# 23_SFP_PORTS.net
KiCad netlist of a schematic drawn in Altium Designer
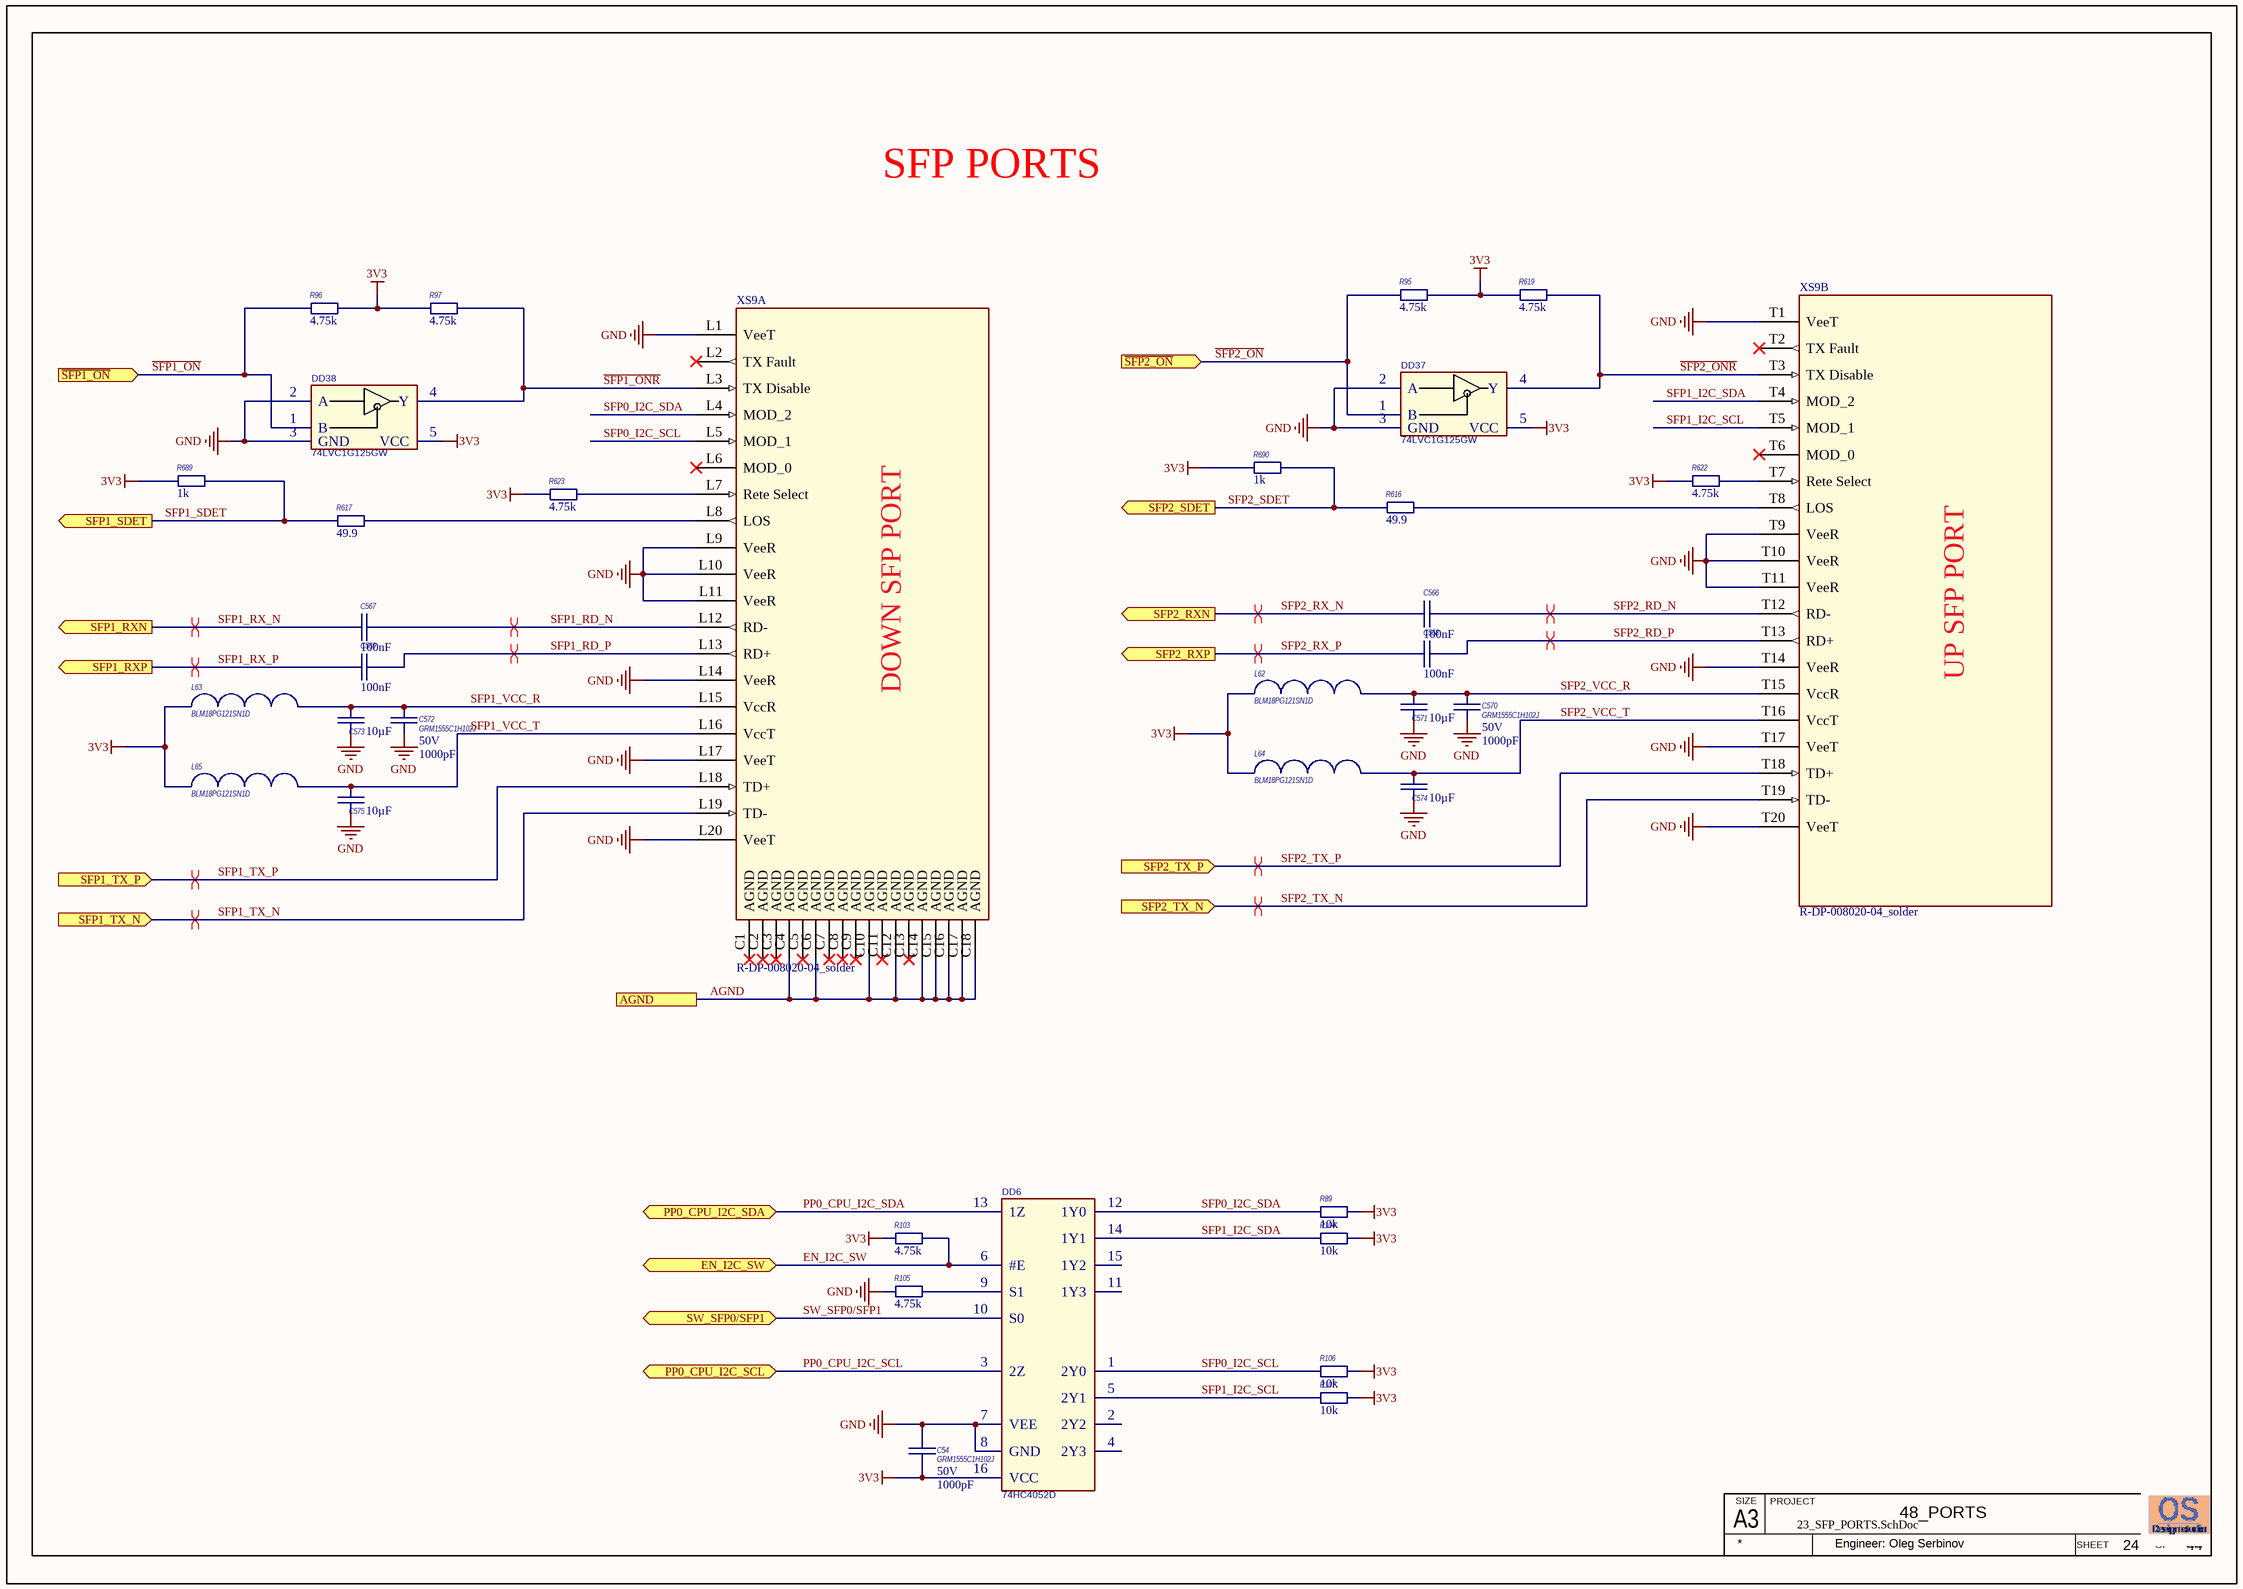
[diagram p0: 23_SFP_PORTS.SchDoc]

(export (version "E")
  (design (tool "Eeschema 10.0.6"))
  (components
    (comp (ref "C54")
      (value "GRM1555C1H102J")
      (footprint "CAPC1005[0402]")
      (description "C0402, 1nF 5%, 50V, C0G")
      (fields
        (field (name "TOLERANCE") "±5%")
        (field (name "MANUFACTURER") "Murata")
        (field (name "VOLTAGE - RATED") "50V")
        (field (name "CAPACITANCE") "1000pF")
      )
      (libsource (lib "CAPACITORS") (part "GRM1555C1H102J"))
    )
    (comp (ref "C566")
      (value "GRM155R71E104KE14D")
      (footprint "C0402_IPC High Density")
      (description "C0402, 100nF, 25V, X7R")
      (fields
        (field (name "MANUFACTURER") "Murata")
        (field (name "CAPACITANCE") "100nF")
        (field (name "CUSTOMER PART NUMBER") "Конденсатор, 100n, 0402, 25V, X7R, 10%")
      )
      (libsource (lib "CAPACITORS") (part "GRM155R71E104KE14D"))
    )
    (comp (ref "C567")
      (value "GRM155R71E104KE14D")
      (footprint "C0402_IPC High Density")
      (description "C0402, 100nF, 25V, X7R")
      (fields
        (field (name "MANUFACTURER") "Murata")
        (field (name "CAPACITANCE") "100nF")
        (field (name "CUSTOMER PART NUMBER") "Конденсатор, 100n, 0402, 25V, X7R, 10%")
      )
      (libsource (lib "CAPACITORS") (part "GRM155R71E104KE14D"))
    )
    (comp (ref "C568")
      (value "GRM155R71E104KE14D")
      (footprint "C0402_IPC High Density")
      (description "C0402, 100nF, 25V, X7R")
      (fields
        (field (name "MANUFACTURER") "Murata")
        (field (name "CAPACITANCE") "100nF")
        (field (name "CUSTOMER PART NUMBER") "Конденсатор, 100n, 0402, 25V, X7R, 10%")
      )
      (libsource (lib "CAPACITORS") (part "GRM155R71E104KE14D"))
    )
    (comp (ref "C569")
      (value "GRM155R71E104KE14D")
      (footprint "C0402_IPC High Density")
      (description "C0402, 100nF, 25V, X7R")
      (fields
        (field (name "MANUFACTURER") "Murata")
        (field (name "CAPACITANCE") "100nF")
        (field (name "CUSTOMER PART NUMBER") "Конденсатор, 100n, 0402, 25V, X7R, 10%")
      )
      (libsource (lib "CAPACITORS") (part "GRM155R71E104KE14D"))
    )
    (comp (ref "C570")
      (value "GRM1555C1H102J")
      (footprint "CAPC1005[0402]")
      (description "C0402, 1nF 5%, 50V, C0G")
      (fields
        (field (name "TOLERANCE") "±5%")
        (field (name "MANUFACTURER") "Murata")
        (field (name "VOLTAGE - RATED") "50V")
        (field (name "CAPACITANCE") "1000pF")
      )
      (libsource (lib "CAPACITORS") (part "GRM1555C1H102J"))
    )
    (comp (ref "C571")
      (value "GRM21BR61C106KE15")
      (footprint "CAPC2012[0805]")
      (description "C0805, 10uF 10%, 16V, X5R")
      (fields
        (field (name "MANUFACTURER") "Murata")
        (field (name "TOLERANCE") "±10%")
        (field (name "CAPACITANCE") "10µF")
      )
      (libsource (lib "CAPACITORS") (part "GRM21BR61C106KE15"))
    )
    (comp (ref "C572")
      (value "GRM1555C1H102J")
      (footprint "CAPC1005[0402]")
      (description "C0402, 1nF 5%, 50V, C0G")
      (fields
        (field (name "TOLERANCE") "±5%")
        (field (name "MANUFACTURER") "Murata")
        (field (name "VOLTAGE - RATED") "50V")
        (field (name "CAPACITANCE") "1000pF")
      )
      (libsource (lib "CAPACITORS") (part "GRM1555C1H102J"))
    )
    (comp (ref "C573")
      (value "GRM21BR61C106KE15")
      (footprint "CAPC2012[0805]")
      (description "C0805, 10uF 10%, 16V, X5R")
      (fields
        (field (name "MANUFACTURER") "Murata")
        (field (name "TOLERANCE") "±10%")
        (field (name "CAPACITANCE") "10µF")
      )
      (libsource (lib "CAPACITORS") (part "GRM21BR61C106KE15"))
    )
    (comp (ref "C574")
      (value "GRM21BR61C106KE15")
      (footprint "CAPC2012[0805]")
      (description "C0805, 10uF 10%, 16V, X5R")
      (fields
        (field (name "MANUFACTURER") "Murata")
        (field (name "TOLERANCE") "±10%")
        (field (name "CAPACITANCE") "10µF")
      )
      (libsource (lib "CAPACITORS") (part "GRM21BR61C106KE15"))
    )
    (comp (ref "C575")
      (value "GRM21BR61C106KE15")
      (footprint "CAPC2012[0805]")
      (description "C0805, 10uF 10%, 16V, X5R")
      (fields
        (field (name "MANUFACTURER") "Murata")
        (field (name "TOLERANCE") "±10%")
        (field (name "CAPACITANCE") "10µF")
      )
      (libsource (lib "CAPACITORS") (part "GRM21BR61C106KE15"))
    )
    (comp (ref "DD6")
      (value "74HC4052D")
      (footprint "SOIC-16")
      (description "IC MUX/DEMUX DUAL 4X1, 16SOIC")
      (fields
        (field (name "CUSTOMER PART NUMBER") "Микросхема, 74HC4052D, IC MUX/DEMUX DUAL 4X1, 16-SOIC")
        (field (name "MANUFACTURER") "NXP Semiconductors")
      )
      (libsource (lib "DIGITAL and ANALIG ICs") (part "74HC4052D"))
    )
    (comp (ref "DD37")
      (value "74LVC1G125GW")
      (footprint "TSSOP5 (SOT353)")
      (description "IC Bus buffer/line driver 3-state, TSSOP5")
      (fields
        (field (name "MANUFACTURER") "NXP Semiconductors")
        (field (name "CUSTOMER PART NUMBER") "Микросхема, 74LVC1G125GW, IC BUFF DVR TRI-ST N-INV, 5-TSSOP")
      )
      (libsource (lib "DIGITAL and ANALIG ICs") (part "74LVC1G125GW"))
    )
    (comp (ref "DD38")
      (value "74LVC1G125GW")
      (footprint "TSSOP5 (SOT353)")
      (description "IC Bus buffer/line driver 3-state, TSSOP5")
      (fields
        (field (name "MANUFACTURER") "NXP Semiconductors")
        (field (name "CUSTOMER PART NUMBER") "Микросхема, 74LVC1G125GW, IC BUFF DVR TRI-ST N-INV, 5-TSSOP")
      )
      (libsource (lib "DIGITAL and ANALIG ICs") (part "74LVC1G125GW"))
    )
    (comp (ref "L62")
      (value "BLM18PG121SN1D")
      (footprint "INDC1608X95N")
      (description "FILTER BLM18 (0603, 2A)")
      (fields
        (field (name "MANUFACTURER") "Murata")
        (field (name "RPART NUMBER") "MPZ1608S121ATAH0 ; CIC10P121NC ; MPZ1608S121ATDH5 ; BLM18PG121SH1D ; 742792625")
      )
      (libsource (lib "INDUCTORS") (part "BLM18PG121SN1D"))
    )
    (comp (ref "L63")
      (value "BLM18PG121SN1D")
      (footprint "INDC1608X95N")
      (description "FILTER BLM18 (0603, 2A)")
      (fields
        (field (name "MANUFACTURER") "Murata")
        (field (name "RPART NUMBER") "MPZ1608S121ATAH0 ; CIC10P121NC ; MPZ1608S121ATDH5 ; BLM18PG121SH1D ; 742792625")
      )
      (libsource (lib "INDUCTORS") (part "BLM18PG121SN1D"))
    )
    (comp (ref "L64")
      (value "BLM18PG121SN1D")
      (footprint "INDC1608X95N")
      (description "FILTER BLM18 (0603, 2A)")
      (fields
        (field (name "MANUFACTURER") "Murata")
        (field (name "RPART NUMBER") "MPZ1608S121ATAH0 ; CIC10P121NC ; MPZ1608S121ATDH5 ; BLM18PG121SH1D ; 742792625")
      )
      (libsource (lib "INDUCTORS") (part "BLM18PG121SN1D"))
    )
    (comp (ref "L65")
      (value "BLM18PG121SN1D")
      (footprint "INDC1608X95N")
      (description "FILTER BLM18 (0603, 2A)")
      (fields
        (field (name "MANUFACTURER") "Murata")
        (field (name "RPART NUMBER") "MPZ1608S121ATAH0 ; CIC10P121NC ; MPZ1608S121ATDH5 ; BLM18PG121SH1D ; 742792625")
      )
      (libsource (lib "INDUCTORS") (part "BLM18PG121SN1D"))
    )
    (comp (ref "R89")
      (value "ERJ-2RKF1002X")
      (footprint "R0402_IPC High Density")
      (description "R0402, 10k 1%")
      (fields
        (field (name "MANUFACTURER") "Panasonic")
        (field (name "TOLERANCE") "1 %")
        (field (name "RESISTANCE") "10k")
      )
      (libsource (lib "RESISTOR") (part "ERJ-2RKF1002X"))
    )
    (comp (ref "R95")
      (value "ERJ-2RKF4751X")
      (footprint "R0402_IPC High Density")
      (description "R0402, 4.75k 1%")
      (fields
        (field (name "TOLERANCE") "±1%")
        (field (name "MANUFACTURER") "Panasonic")
        (field (name "RESISTANCE (OHMS)") "4.75k")
      )
      (libsource (lib "RESISTOR") (part "ERJ-2RKF4751X"))
    )
    (comp (ref "R96")
      (value "ERJ-2RKF4751X")
      (footprint "R0402_IPC High Density")
      (description "R0402, 4.75k 1%")
      (fields
        (field (name "TOLERANCE") "±1%")
        (field (name "MANUFACTURER") "Panasonic")
        (field (name "RESISTANCE (OHMS)") "4.75k")
      )
      (libsource (lib "RESISTOR") (part "ERJ-2RKF4751X"))
    )
    (comp (ref "R97")
      (value "ERJ-2RKF4751X")
      (footprint "R0402_IPC High Density")
      (description "R0402, 4.75k 1%")
      (fields
        (field (name "TOLERANCE") "±1%")
        (field (name "MANUFACTURER") "Panasonic")
        (field (name "RESISTANCE (OHMS)") "4.75k")
      )
      (libsource (lib "RESISTOR") (part "ERJ-2RKF4751X"))
    )
    (comp (ref "R103")
      (value "ERJ-2RKF4751X")
      (footprint "R0402_IPC High Density")
      (description "R0402, 4.75k 1%")
      (fields
        (field (name "TOLERANCE") "±1%")
        (field (name "MANUFACTURER") "Panasonic")
        (field (name "RESISTANCE (OHMS)") "4.75k")
      )
      (libsource (lib "RESISTOR") (part "ERJ-2RKF4751X"))
    )
    (comp (ref "R104")
      (value "ERJ-2RKF1002X")
      (footprint "R0402_IPC High Density")
      (description "R0402, 10k 1%")
      (fields
        (field (name "MANUFACTURER") "Panasonic")
        (field (name "TOLERANCE") "1 %")
        (field (name "RESISTANCE") "10k")
      )
      (libsource (lib "RESISTOR") (part "ERJ-2RKF1002X"))
    )
    (comp (ref "R105")
      (value "ERJ-2RKF4751X")
      (footprint "R0402_IPC High Density")
      (description "R0402, 4.75k 1%")
      (fields
        (field (name "TOLERANCE") "±1%")
        (field (name "MANUFACTURER") "Panasonic")
        (field (name "RESISTANCE (OHMS)") "4.75k")
      )
      (libsource (lib "RESISTOR") (part "ERJ-2RKF4751X"))
    )
    (comp (ref "R106")
      (value "ERJ-2RKF1002X")
      (footprint "R0402_IPC High Density")
      (description "R0402, 10k 1%")
      (fields
        (field (name "MANUFACTURER") "Panasonic")
        (field (name "TOLERANCE") "1 %")
        (field (name "RESISTANCE") "10k")
      )
      (libsource (lib "RESISTOR") (part "ERJ-2RKF1002X"))
    )
    (comp (ref "R107")
      (value "ERJ-2RKF1002X")
      (footprint "R0402_IPC High Density")
      (description "R0402, 10k 1%")
      (fields
        (field (name "MANUFACTURER") "Panasonic")
        (field (name "TOLERANCE") "1 %")
        (field (name "RESISTANCE") "10k")
      )
      (libsource (lib "RESISTOR") (part "ERJ-2RKF1002X"))
    )
    (comp (ref "R616")
      (value "ERJ-2RKF49R9X")
      (footprint "R0402_IPC High Density")
      (description "R0402, 49.9R 1%")
      (fields
        (field (name "MANUFACTURER") "Panasonic")
        (field (name "TOLERANCE") "1 %")
        (field (name "RESISTANCE") "49.9")
      )
      (libsource (lib "RESISTOR") (part "ERJ-2RKF49R9X"))
    )
    (comp (ref "R617")
      (value "ERJ-2RKF49R9X")
      (footprint "R0402_IPC High Density")
      (description "R0402, 49.9R 1%")
      (fields
        (field (name "MANUFACTURER") "Panasonic")
        (field (name "TOLERANCE") "1 %")
        (field (name "RESISTANCE") "49.9")
      )
      (libsource (lib "RESISTOR") (part "ERJ-2RKF49R9X"))
    )
    (comp (ref "R619")
      (value "ERJ-2RKF4751X")
      (footprint "R0402_IPC High Density")
      (description "R0402, 4.75k 1%")
      (fields
        (field (name "TOLERANCE") "±1%")
        (field (name "MANUFACTURER") "Panasonic")
        (field (name "RESISTANCE (OHMS)") "4.75k")
      )
      (libsource (lib "RESISTOR") (part "ERJ-2RKF4751X"))
    )
    (comp (ref "R622")
      (value "ERJ-2RKF4751X")
      (footprint "R0402_IPC High Density")
      (description "R0402, 4.75k 1%")
      (fields
        (field (name "TOLERANCE") "±1%")
        (field (name "MANUFACTURER") "Panasonic")
        (field (name "RESISTANCE (OHMS)") "4.75k")
      )
      (libsource (lib "RESISTOR") (part "ERJ-2RKF4751X"))
    )
    (comp (ref "R623")
      (value "ERJ-2RKF4751X")
      (footprint "R0402_IPC High Density")
      (description "R0402, 4.75k 1%")
      (fields
        (field (name "TOLERANCE") "±1%")
        (field (name "MANUFACTURER") "Panasonic")
        (field (name "RESISTANCE (OHMS)") "4.75k")
      )
      (libsource (lib "RESISTOR") (part "ERJ-2RKF4751X"))
    )
    (comp (ref "R689")
      (value "ERJ-2RKF1001X")
      (footprint "R0402_IPC High Density")
      (description "R0402, 1k 1%")
      (fields
        (field (name "MANUFACTURER") "Panasonic")
        (field (name "TOLERANCE") "1 %")
        (field (name "RESISTANCE") "1k")
      )
      (libsource (lib "RESISTOR") (part "ERJ-2RKF1001X"))
    )
    (comp (ref "R690")
      (value "ERJ-2RKF1001X")
      (footprint "R0402_IPC High Density")
      (description "R0402, 1k 1%")
      (fields
        (field (name "MANUFACTURER") "Panasonic")
        (field (name "TOLERANCE") "1 %")
        (field (name "RESISTANCE") "1k")
      )
      (libsource (lib "RESISTOR") (part "ERJ-2RKF1001X"))
    )
    (comp (ref "XS9")
      (value "R-DP-008020-04_solder")
      (footprint "R-DP-008020-04_solder")
      (description "Connector SFP CAGE 2X1 PRESS FIT")
      (fields
        (field (name "CUSTOMER PART NUMBER") "Разъем, R-DP-008020-04, SFP 2X1 Stacked Cage, PRESS FIT")
        (field (name "MANUFACTURER") "ALL BEST")
      )
      (libsource (lib "CONNECTORS") (part "R-DP-008020-04_solder"))
    )
  )
  (nets
    (net (code "1") (name "/AGND") (class "Default")
      (node (ref "XS9") (pin "C10") (pinfunction "AGND_C10") (pintype "power_in"))
      (node (ref "XS9") (pin "C12") (pinfunction "AGND_C12") (pintype "power_in"))
      (node (ref "XS9") (pin "C14") (pinfunction "AGND_C14") (pintype "power_in"))
      (node (ref "XS9") (pin "C15") (pinfunction "AGND_C15") (pintype "power_in"))
      (node (ref "XS9") (pin "C16") (pinfunction "AGND_C16") (pintype "power_in"))
      (node (ref "XS9") (pin "C17") (pinfunction "AGND_C17") (pintype "power_in"))
      (node (ref "XS9") (pin "C18") (pinfunction "AGND_C18") (pintype "power_in"))
      (node (ref "XS9") (pin "C4") (pinfunction "AGND_C4") (pintype "power_in"))
      (node (ref "XS9") (pin "C6") (pinfunction "AGND_C6") (pintype "power_in"))
    )
    (net (code "2") (name "/EN_I2C_SW") (class "Default")
      (node (ref "DD6") (pin "6") (pinfunction "#E_6") (pintype "passive"))
      (node (ref "R103") (pin "2") (pintype "passive"))
    )
    (net (code "3") (name "/PP0_CPU_I2C_SCL") (class "Default")
      (node (ref "DD6") (pin "3") (pinfunction "2Z_3") (pintype "passive"))
    )
    (net (code "4") (name "/PP0_CPU_I2C_SDA") (class "Default")
      (node (ref "DD6") (pin "13") (pinfunction "1Z_13") (pintype "passive"))
    )
    (net (code "5") (name "/SFP0_I2C_SCL") (class "Default")
      (node (ref "DD6") (pin "1") (pinfunction "2Y0_1") (pintype "passive"))
      (node (ref "R106") (pin "2") (pintype "passive"))
      (node (ref "XS9") (pin "L5") (pinfunction "MOD_1_L5") (pintype "input"))
    )
    (net (code "6") (name "/SFP0_I2C_SDA") (class "Default")
      (node (ref "DD6") (pin "12") (pinfunction "1Y0_12") (pintype "passive"))
      (node (ref "R89") (pin "2") (pintype "passive"))
      (node (ref "XS9") (pin "L4") (pinfunction "MOD_2_L4") (pintype "input"))
    )
    (net (code "7") (name "/SFP1_I2C_SCL") (class "Default")
      (node (ref "DD6") (pin "5") (pinfunction "2Y1_5") (pintype "passive"))
      (node (ref "R107") (pin "2") (pintype "passive"))
      (node (ref "XS9") (pin "T5") (pinfunction "MOD_1_T5") (pintype "input"))
    )
    (net (code "8") (name "/SFP1_I2C_SDA") (class "Default")
      (node (ref "DD6") (pin "14") (pinfunction "1Y1_14") (pintype "passive"))
      (node (ref "R104") (pin "2") (pintype "passive"))
      (node (ref "XS9") (pin "T4") (pinfunction "MOD_2_T4") (pintype "input"))
    )
    (net (code "9") (name "/SFP1_ON") (class "Default")
      (node (ref "DD38") (pin "1") (pinfunction "B_1") (pintype "passive"))
      (node (ref "R96") (pin "1") (pintype "passive"))
    )
    (net (code "10") (name "/SFP1_ONR") (class "Default")
      (node (ref "DD38") (pin "4") (pinfunction "Y_4") (pintype "passive"))
      (node (ref "R97") (pin "2") (pintype "passive"))
      (node (ref "XS9") (pin "L3") (pinfunction "TX_Disable_L3") (pintype "input"))
    )
    (net (code "11") (name "/SFP1_RD_N") (class "Default")
      (node (ref "C567") (pin "1") (pintype "passive"))
      (node (ref "XS9") (pin "L12") (pinfunction "RD-_L12") (pintype "output"))
    )
    (net (code "12") (name "/SFP1_RD_P") (class "Default")
      (node (ref "C569") (pin "1") (pintype "passive"))
      (node (ref "XS9") (pin "L13") (pinfunction "RD+_L13") (pintype "output"))
    )
    (net (code "13") (name "/SFP1_RX_N") (class "Default") (node (ref "C567") (pin "2") (pintype "passive")))
    (net (code "14") (name "/SFP1_RX_P") (class "Default") (node (ref "C569") (pin "2") (pintype "passive")))
    (net (code "15") (name "/SFP1_SDET") (class "Default")
      (node (ref "R617") (pin "1") (pintype "passive"))
      (node (ref "R689") (pin "2") (pintype "passive"))
    )
    (net (code "16") (name "/SFP1_TX_N") (class "Default")
      (node (ref "XS9") (pin "L19") (pinfunction "TD-_L19") (pintype "input"))
    )
    (net (code "17") (name "/SFP1_TX_P") (class "Default")
      (node (ref "XS9") (pin "L18") (pinfunction "TD+_L18") (pintype "input"))
    )
    (net (code "18") (name "/SFP1_VCC_R") (class "Default")
      (node (ref "C572") (pin "2") (pintype "passive"))
      (node (ref "C573") (pin "2") (pintype "passive"))
      (node (ref "L63") (pin "2") (pinfunction "2_2") (pintype "passive"))
      (node (ref "XS9") (pin "L15") (pinfunction "VccR_L15") (pintype "power_in"))
    )
    (net (code "19") (name "/SFP1_VCC_T") (class "Default")
      (node (ref "C575") (pin "1") (pintype "passive"))
      (node (ref "L65") (pin "2") (pinfunction "2_2") (pintype "passive"))
      (node (ref "XS9") (pin "L16") (pinfunction "VccT_L16") (pintype "power_in"))
    )
    (net (code "20") (name "/SFP2_ON") (class "Default")
      (node (ref "DD37") (pin "1") (pinfunction "B_1") (pintype "passive"))
      (node (ref "R95") (pin "1") (pintype "passive"))
    )
    (net (code "21") (name "/SFP2_ONR") (class "Default")
      (node (ref "DD37") (pin "4") (pinfunction "Y_4") (pintype "passive"))
      (node (ref "R619") (pin "2") (pintype "passive"))
      (node (ref "XS9") (pin "T3") (pinfunction "TX_Disable_T3") (pintype "input"))
    )
    (net (code "22") (name "/SFP2_RD_N") (class "Default")
      (node (ref "C566") (pin "1") (pintype "passive"))
      (node (ref "XS9") (pin "T12") (pinfunction "RD-_T12") (pintype "output"))
    )
    (net (code "23") (name "/SFP2_RD_P") (class "Default")
      (node (ref "C568") (pin "1") (pintype "passive"))
      (node (ref "XS9") (pin "T13") (pinfunction "RD+_T13") (pintype "output"))
    )
    (net (code "24") (name "/SFP2_RX_N") (class "Default") (node (ref "C566") (pin "2") (pintype "passive")))
    (net (code "25") (name "/SFP2_RX_P") (class "Default") (node (ref "C568") (pin "2") (pintype "passive")))
    (net (code "26") (name "/SFP2_SDET") (class "Default")
      (node (ref "R616") (pin "1") (pintype "passive"))
      (node (ref "R690") (pin "2") (pintype "passive"))
    )
    (net (code "27") (name "/SFP2_TX_N") (class "Default")
      (node (ref "XS9") (pin "T19") (pinfunction "TD-_T19") (pintype "input"))
    )
    (net (code "28") (name "/SFP2_TX_P") (class "Default")
      (node (ref "XS9") (pin "T18") (pinfunction "TD+_T18") (pintype "input"))
    )
    (net (code "29") (name "/SFP2_VCC_R") (class "Default")
      (node (ref "C570") (pin "2") (pintype "passive"))
      (node (ref "C571") (pin "2") (pintype "passive"))
      (node (ref "L62") (pin "2") (pinfunction "2_2") (pintype "passive"))
      (node (ref "XS9") (pin "T15") (pinfunction "VccR_T15") (pintype "power_in"))
    )
    (net (code "30") (name "/SFP2_VCC_T") (class "Default")
      (node (ref "C574") (pin "1") (pintype "passive"))
      (node (ref "L64") (pin "2") (pinfunction "2_2") (pintype "passive"))
      (node (ref "XS9") (pin "T16") (pinfunction "VccT_T16") (pintype "power_in"))
    )
    (net (code "31") (name "/SW_SFP0{slash}SFP1") (class "Default")
      (node (ref "DD6") (pin "10") (pinfunction "S0_10") (pintype "passive"))
    )
    (net (code "32") (name "3V3") (class "Default")
      (node (ref "C54") (pin "2") (pintype "passive"))
      (node (ref "DD37") (pin "5") (pinfunction "VCC_5") (pintype "passive"))
      (node (ref "DD38") (pin "5") (pinfunction "VCC_5") (pintype "passive"))
      (node (ref "DD6") (pin "16") (pinfunction "VCC_16") (pintype "passive"))
      (node (ref "L62") (pin "1") (pinfunction "1_1") (pintype "passive"))
      (node (ref "L63") (pin "1") (pinfunction "1_1") (pintype "passive"))
      (node (ref "L64") (pin "1") (pinfunction "1_1") (pintype "passive"))
      (node (ref "L65") (pin "1") (pinfunction "1_1") (pintype "passive"))
      (node (ref "R103") (pin "1") (pintype "passive"))
      (node (ref "R104") (pin "1") (pintype "passive"))
      (node (ref "R106") (pin "1") (pintype "passive"))
      (node (ref "R107") (pin "1") (pintype "passive"))
      (node (ref "R619") (pin "1") (pintype "passive"))
      (node (ref "R622") (pin "1") (pintype "passive"))
      (node (ref "R623") (pin "1") (pintype "passive"))
      (node (ref "R689") (pin "1") (pintype "passive"))
      (node (ref "R690") (pin "1") (pintype "passive"))
      (node (ref "R89") (pin "1") (pintype "passive"))
      (node (ref "R95") (pin "2") (pintype "passive"))
      (node (ref "R96") (pin "2") (pintype "passive"))
      (node (ref "R97") (pin "1") (pintype "passive"))
    )
    (net (code "33") (name "GND") (class "Default")
      (node (ref "C54") (pin "1") (pintype "passive"))
      (node (ref "C570") (pin "1") (pintype "passive"))
      (node (ref "C571") (pin "1") (pintype "passive"))
      (node (ref "C572") (pin "1") (pintype "passive"))
      (node (ref "C573") (pin "1") (pintype "passive"))
      (node (ref "C574") (pin "2") (pintype "passive"))
      (node (ref "C575") (pin "2") (pintype "passive"))
      (node (ref "DD37") (pin "2") (pinfunction "A_2") (pintype "passive"))
      (node (ref "DD37") (pin "3") (pinfunction "GND_3") (pintype "passive"))
      (node (ref "DD38") (pin "2") (pinfunction "A_2") (pintype "passive"))
      (node (ref "DD38") (pin "3") (pinfunction "GND_3") (pintype "passive"))
      (node (ref "DD6") (pin "7") (pinfunction "VEE_7") (pintype "passive"))
      (node (ref "DD6") (pin "8") (pinfunction "GND_8") (pintype "passive"))
      (node (ref "R105") (pin "1") (pintype "passive"))
      (node (ref "XS9") (pin "L1") (pinfunction "VeeT_L1") (pintype "power_in"))
      (node (ref "XS9") (pin "L10") (pinfunction "VeeR_L10") (pintype "power_in"))
      (node (ref "XS9") (pin "L11") (pinfunction "VeeR_L11") (pintype "power_in"))
      (node (ref "XS9") (pin "L14") (pinfunction "VeeR_L14") (pintype "power_in"))
      (node (ref "XS9") (pin "L17") (pinfunction "VeeT_L17") (pintype "power_in"))
      (node (ref "XS9") (pin "L20") (pinfunction "VeeT_L20") (pintype "power_in"))
      (node (ref "XS9") (pin "L9") (pinfunction "VeeR_L9") (pintype "power_in"))
      (node (ref "XS9") (pin "T1") (pinfunction "VeeT_T1") (pintype "power_in"))
      (node (ref "XS9") (pin "T10") (pinfunction "VeeR_T10") (pintype "power_in"))
      (node (ref "XS9") (pin "T11") (pinfunction "VeeR_T11") (pintype "power_in"))
      (node (ref "XS9") (pin "T14") (pinfunction "VeeR_T14") (pintype "power_in"))
      (node (ref "XS9") (pin "T17") (pinfunction "VeeT_T17") (pintype "power_in"))
      (node (ref "XS9") (pin "T20") (pinfunction "VeeT_T20") (pintype "power_in"))
      (node (ref "XS9") (pin "T9") (pinfunction "VeeR_T9") (pintype "power_in"))
    )
    (net (code "34") (name "Net-(DD6-S1)") (class "Default")
      (node (ref "DD6") (pin "9") (pinfunction "S1_9") (pintype "passive"))
      (node (ref "R105") (pin "2") (pintype "passive"))
    )
    (net (code "35") (name "Net-(XS9A-LOS)") (class "Default")
      (node (ref "R617") (pin "2") (pintype "passive"))
      (node (ref "XS9") (pin "L8") (pinfunction "LOS_L8") (pintype "output"))
    )
    (net (code "36") (name "Net-(XS9A-Rete_Select)") (class "Default")
      (node (ref "R623") (pin "2") (pintype "passive"))
      (node (ref "XS9") (pin "L7") (pinfunction "Rete_Select_L7") (pintype "input"))
    )
    (net (code "37") (name "Net-(XS9B-LOS)") (class "Default")
      (node (ref "R616") (pin "2") (pintype "passive"))
      (node (ref "XS9") (pin "T8") (pinfunction "LOS_T8") (pintype "output"))
    )
    (net (code "38") (name "Net-(XS9B-Rete_Select)") (class "Default")
      (node (ref "R622") (pin "2") (pintype "passive"))
      (node (ref "XS9") (pin "T7") (pinfunction "Rete_Select_T7") (pintype "input"))
    )
    (net (code "39") (name "unconnected-(DD6-1Y2-Pad15)") (class "Default")
      (node (ref "DD6") (pin "15") (pinfunction "1Y2_15") (pintype "passive"))
    )
    (net (code "40") (name "unconnected-(DD6-1Y3-Pad11)") (class "Default")
      (node (ref "DD6") (pin "11") (pinfunction "1Y3_11") (pintype "passive"))
    )
    (net (code "41") (name "unconnected-(DD6-2Y2-Pad2)") (class "Default")
      (node (ref "DD6") (pin "2") (pinfunction "2Y2_2") (pintype "passive"))
    )
    (net (code "42") (name "unconnected-(DD6-2Y3-Pad4)") (class "Default")
      (node (ref "DD6") (pin "4") (pinfunction "2Y3_4") (pintype "passive"))
    )
    (net (code "43") (name "unconnected-(XS9A-AGND-PadC1)") (class "Default")
      (node (ref "XS9") (pin "C1") (pinfunction "AGND_C1") (pintype "power_in+no_connect"))
    )
    (net (code "44") (name "unconnected-(XS9A-AGND-PadC2)") (class "Default")
      (node (ref "XS9") (pin "C2") (pinfunction "AGND_C2") (pintype "power_in+no_connect"))
    )
    (net (code "45") (name "unconnected-(XS9A-AGND-PadC3)") (class "Default")
      (node (ref "XS9") (pin "C3") (pinfunction "AGND_C3") (pintype "power_in+no_connect"))
    )
    (net (code "46") (name "unconnected-(XS9A-AGND-PadC5)") (class "Default")
      (node (ref "XS9") (pin "C5") (pinfunction "AGND_C5") (pintype "power_in+no_connect"))
    )
    (net (code "47") (name "unconnected-(XS9A-AGND-PadC7)") (class "Default")
      (node (ref "XS9") (pin "C7") (pinfunction "AGND_C7") (pintype "power_in+no_connect"))
    )
    (net (code "48") (name "unconnected-(XS9A-AGND-PadC8)") (class "Default")
      (node (ref "XS9") (pin "C8") (pinfunction "AGND_C8") (pintype "power_in+no_connect"))
    )
    (net (code "49") (name "unconnected-(XS9A-AGND-PadC9)") (class "Default")
      (node (ref "XS9") (pin "C9") (pinfunction "AGND_C9") (pintype "power_in+no_connect"))
    )
    (net (code "50") (name "unconnected-(XS9A-AGND-PadC11)") (class "Default")
      (node (ref "XS9") (pin "C11") (pinfunction "AGND_C11") (pintype "power_in+no_connect"))
    )
    (net (code "51") (name "unconnected-(XS9A-AGND-PadC13)") (class "Default")
      (node (ref "XS9") (pin "C13") (pinfunction "AGND_C13") (pintype "power_in+no_connect"))
    )
    (net (code "52") (name "unconnected-(XS9A-MOD_0-PadL6)") (class "Default")
      (node (ref "XS9") (pin "L6") (pinfunction "MOD_0_L6") (pintype "passive+no_connect"))
    )
    (net (code "53") (name "unconnected-(XS9A-TX_Fault-PadL2)") (class "Default")
      (node (ref "XS9") (pin "L2") (pinfunction "TX_Fault_L2") (pintype "output+no_connect"))
    )
    (net (code "54") (name "unconnected-(XS9B-MOD_0-PadT6)") (class "Default")
      (node (ref "XS9") (pin "T6") (pinfunction "MOD_0_T6") (pintype "passive+no_connect"))
    )
    (net (code "55") (name "unconnected-(XS9B-TX_Fault-PadT2)") (class "Default")
      (node (ref "XS9") (pin "T2") (pinfunction "TX_Fault_T2") (pintype "output+no_connect"))
    )
  )
)
